# Logic_Level_Bidirectional.net
KiCad netlist of a schematic drawn in EAGLE
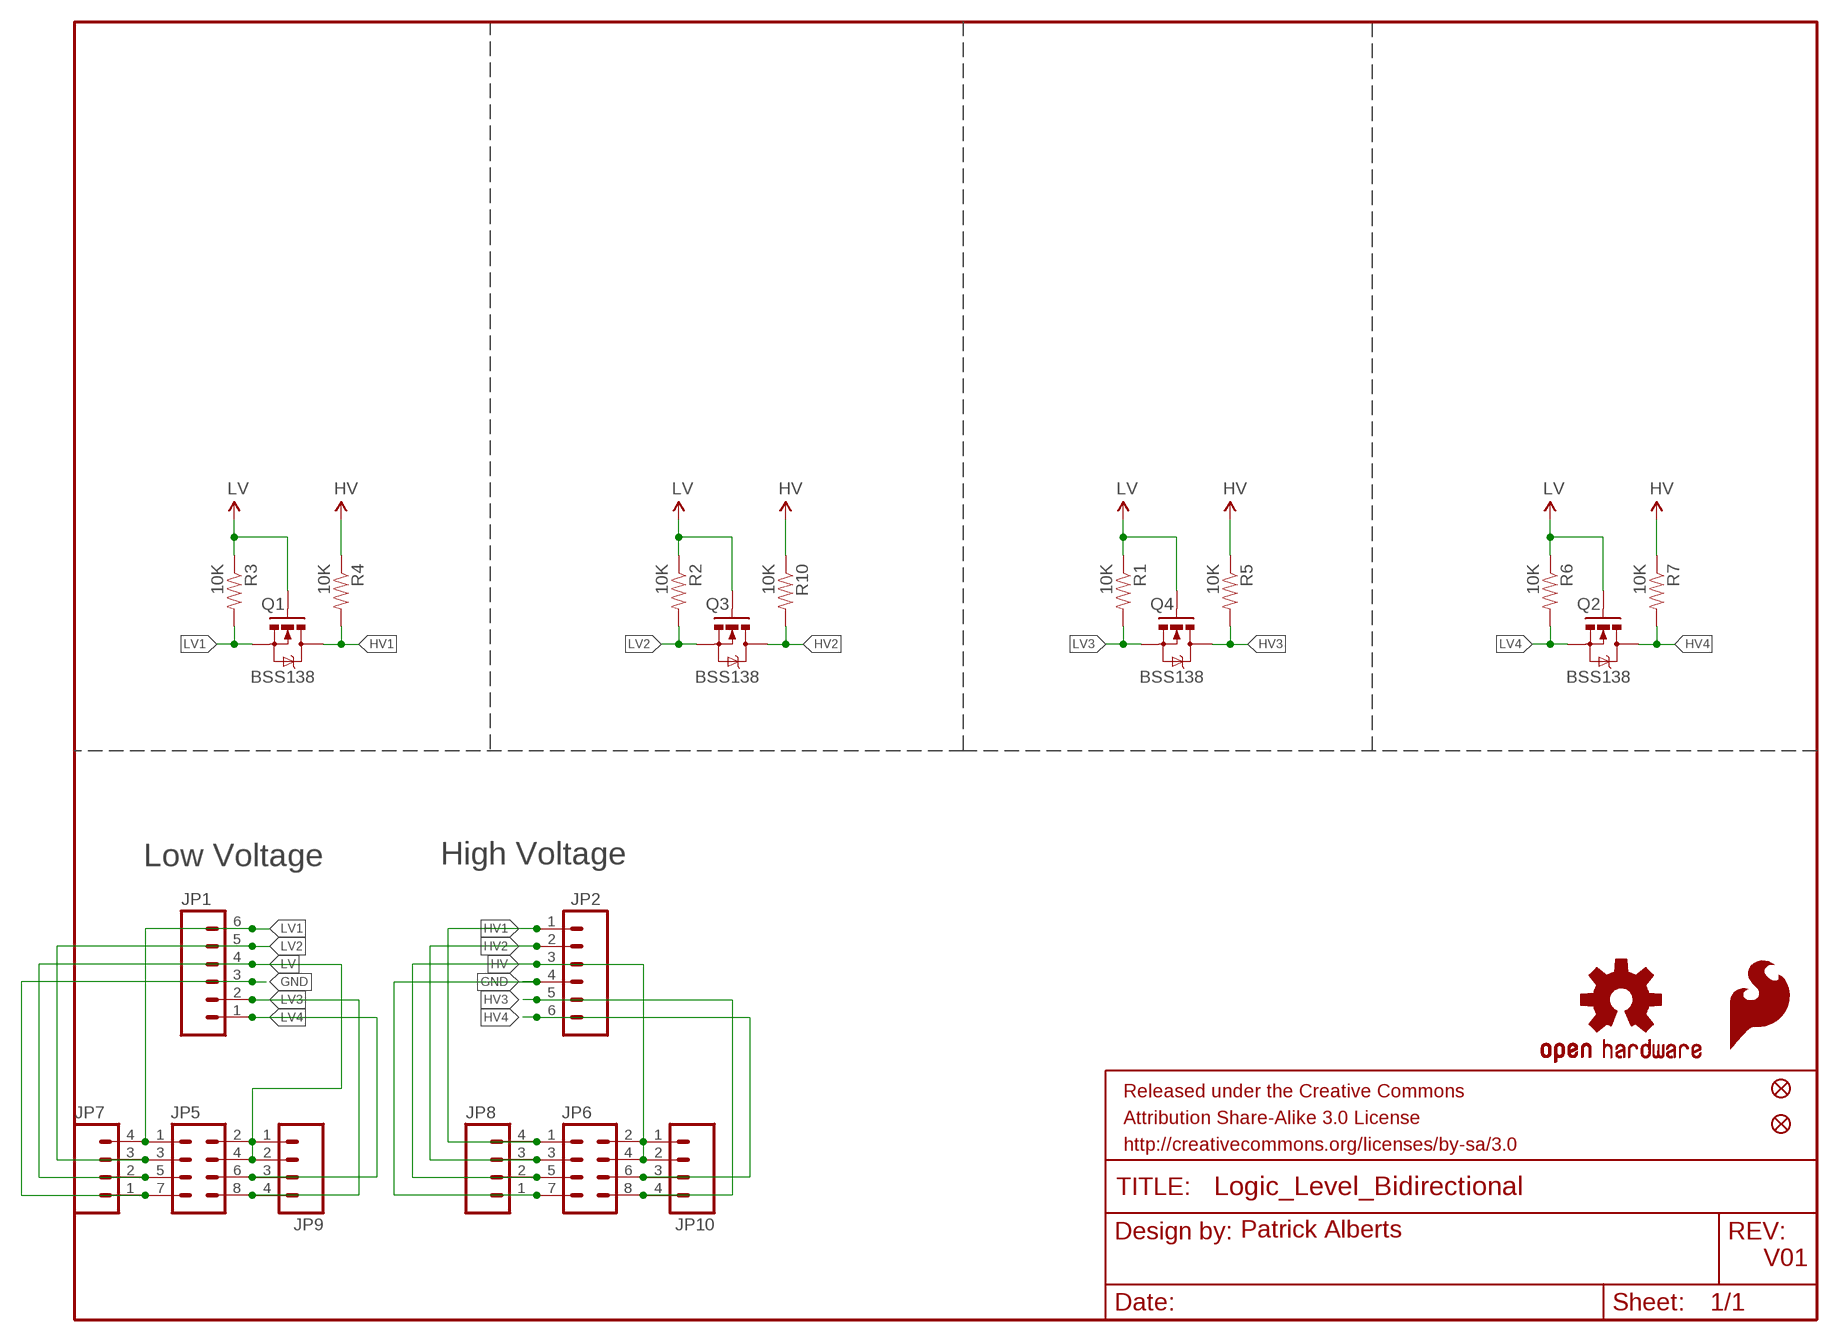
[diagram p0: schematic, sheet 1]

(export (version "E")
  (design (tool "Eeschema 10.0.6"))
  (components
    (comp (ref "JP1")
      (value "M06SIP")
      (footprint "eagle-import:1X06")
      (libsource (lib "eagle-import") (part "M06SIP"))
    )
    (comp (ref "JP2")
      (value "M06SIP")
      (footprint "eagle-import:1X06")
      (libsource (lib "eagle-import") (part "M06SIP"))
    )
    (comp (ref "JP3")
      (value "FIDUCIALUFIDUCIAL")
      (footprint "eagle-import:MICRO-FIDUCIAL")
      (libsource (lib "eagle-import") (part "FIDUCIALUFIDUCIAL"))
    )
    (comp (ref "JP4")
      (value "FIDUCIALUFIDUCIAL")
      (footprint "eagle-import:MICRO-FIDUCIAL")
      (libsource (lib "eagle-import") (part "FIDUCIALUFIDUCIAL"))
    )
    (comp (ref "JP5")
      (value "M04X2")
      (footprint "eagle-import:2X4")
      (libsource (lib "eagle-import") (part "M04X2"))
    )
    (comp (ref "JP6")
      (value "M04X2")
      (footprint "eagle-import:2X4")
      (libsource (lib "eagle-import") (part "M04X2"))
    )
    (comp (ref "JP7")
      (value "M04LOCK")
      (footprint "eagle-import:1X04_LOCK")
      (libsource (lib "eagle-import") (part "M04LOCK"))
    )
    (comp (ref "JP8")
      (value "M04LOCK")
      (footprint "eagle-import:1X04_LOCK")
      (libsource (lib "eagle-import") (part "M04LOCK"))
    )
    (comp (ref "JP9")
      (value "M04PTH")
      (footprint "eagle-import:1X04")
      (libsource (lib "eagle-import") (part "M04PTH"))
    )
    (comp (ref "JP10")
      (value "M04PTH")
      (footprint "eagle-import:1X04")
      (libsource (lib "eagle-import") (part "M04PTH"))
    )
    (comp (ref "LOGO1")
      (value "SFE_LOGO_FLAME.1_INCH")
      (footprint "eagle-import:SFE_LOGO_FLAME_.1")
      (libsource (lib "eagle-import") (part "SFE_LOGO_FLAME.1_INCH"))
    )
    (comp (ref "LOGO2")
      (value "OSHW-LOGOS")
      (footprint "eagle-import:OSHW-LOGO-S")
      (libsource (lib "eagle-import") (part "OSHW-LOGOS"))
    )
    (comp (ref "Q1")
      (value "BSS138")
      (footprint "eagle-import:SOT23-3")
      (libsource (lib "eagle-import") (part "MOSFET-NCHANNELSMD"))
    )
    (comp (ref "Q2")
      (value "BSS138")
      (footprint "eagle-import:SOT23-3")
      (libsource (lib "eagle-import") (part "MOSFET-NCHANNELSMD"))
    )
    (comp (ref "Q3")
      (value "BSS138")
      (footprint "eagle-import:SOT23-3")
      (libsource (lib "eagle-import") (part "MOSFET-NCHANNELSMD"))
    )
    (comp (ref "Q4")
      (value "BSS138")
      (footprint "eagle-import:SOT23-3")
      (libsource (lib "eagle-import") (part "MOSFET-NCHANNELSMD"))
    )
    (comp (ref "R1")
      (value "10K")
      (footprint "eagle-import:0603-RES")
      (libsource (lib "eagle-import") (part "RESISTOR0603-RES"))
    )
    (comp (ref "R2")
      (value "10K")
      (footprint "eagle-import:0603-RES")
      (libsource (lib "eagle-import") (part "RESISTOR0603-RES"))
    )
    (comp (ref "R3")
      (value "10K")
      (footprint "eagle-import:0603-RES")
      (libsource (lib "eagle-import") (part "RESISTOR0603-RES"))
    )
    (comp (ref "R4")
      (value "10K")
      (footprint "eagle-import:0603-RES")
      (libsource (lib "eagle-import") (part "RESISTOR0603-RES"))
    )
    (comp (ref "R5")
      (value "10K")
      (footprint "eagle-import:0603-RES")
      (libsource (lib "eagle-import") (part "RESISTOR0603-RES"))
    )
    (comp (ref "R6")
      (value "10K")
      (footprint "eagle-import:0603-RES")
      (libsource (lib "eagle-import") (part "RESISTOR0603-RES"))
    )
    (comp (ref "R7")
      (value "10K")
      (footprint "eagle-import:0603-RES")
      (libsource (lib "eagle-import") (part "RESISTOR0603-RES"))
    )
    (comp (ref "R10")
      (value "10K")
      (footprint "eagle-import:0603-RES")
      (libsource (lib "eagle-import") (part "RESISTOR0603-RES"))
    )
  )
  (nets
    (net (code "1") (name "GND") (class "Default")
      (node (ref "JP1") (pin "3") (pinfunction "3_3") (pintype "passive"))
      (node (ref "JP2") (pin "4") (pinfunction "4_4") (pintype "passive"))
      (node (ref "JP5") (pin "7") (pinfunction "7_7") (pintype "passive"))
      (node (ref "JP6") (pin "7") (pinfunction "7_7") (pintype "passive"))
      (node (ref "JP7") (pin "1") (pinfunction "1_1") (pintype "passive"))
      (node (ref "JP8") (pin "1") (pinfunction "1_1") (pintype "passive"))
    )
    (net (code "2") (name "HV") (class "Default")
      (node (ref "JP10") (pin "1") (pinfunction "1_1") (pintype "passive"))
      (node (ref "JP10") (pin "2") (pinfunction "2_2") (pintype "passive"))
      (node (ref "JP2") (pin "3") (pinfunction "3_3") (pintype "passive"))
      (node (ref "JP6") (pin "2") (pinfunction "2_2") (pintype "passive"))
      (node (ref "JP6") (pin "4") (pinfunction "4_4") (pintype "passive"))
      (node (ref "JP6") (pin "5") (pinfunction "5_5") (pintype "passive"))
      (node (ref "JP8") (pin "2") (pinfunction "2_2") (pintype "passive"))
      (node (ref "R10") (pin "1") (pinfunction "1_1") (pintype "passive"))
      (node (ref "R4") (pin "1") (pinfunction "1_1") (pintype "passive"))
      (node (ref "R5") (pin "1") (pinfunction "1_1") (pintype "passive"))
      (node (ref "R7") (pin "1") (pinfunction "1_1") (pintype "passive"))
    )
    (net (code "3") (name "HV1") (class "Default")
      (node (ref "JP2") (pin "1") (pinfunction "1_1") (pintype "passive"))
      (node (ref "JP6") (pin "1") (pinfunction "1_1") (pintype "passive"))
      (node (ref "JP8") (pin "4") (pinfunction "4_4") (pintype "passive"))
      (node (ref "Q1") (pin "3") (pinfunction "D_3") (pintype "passive"))
      (node (ref "R4") (pin "2") (pinfunction "2_2") (pintype "passive"))
    )
    (net (code "4") (name "HV2") (class "Default")
      (node (ref "JP2") (pin "2") (pinfunction "2_2") (pintype "passive"))
      (node (ref "JP6") (pin "3") (pinfunction "3_3") (pintype "passive"))
      (node (ref "JP8") (pin "3") (pinfunction "3_3") (pintype "passive"))
      (node (ref "Q3") (pin "3") (pinfunction "D_3") (pintype "passive"))
      (node (ref "R10") (pin "2") (pinfunction "2_2") (pintype "passive"))
    )
    (net (code "5") (name "HV3") (class "Default")
      (node (ref "JP10") (pin "4") (pinfunction "4_4") (pintype "passive"))
      (node (ref "JP2") (pin "5") (pinfunction "5_5") (pintype "passive"))
      (node (ref "JP6") (pin "8") (pinfunction "8_8") (pintype "passive"))
      (node (ref "Q4") (pin "3") (pinfunction "D_3") (pintype "passive"))
      (node (ref "R5") (pin "2") (pinfunction "2_2") (pintype "passive"))
    )
    (net (code "6") (name "HV4") (class "Default")
      (node (ref "JP10") (pin "3") (pinfunction "3_3") (pintype "passive"))
      (node (ref "JP2") (pin "6") (pinfunction "6_6") (pintype "passive"))
      (node (ref "JP6") (pin "6") (pinfunction "6_6") (pintype "passive"))
      (node (ref "Q2") (pin "3") (pinfunction "D_3") (pintype "passive"))
      (node (ref "R7") (pin "2") (pinfunction "2_2") (pintype "passive"))
    )
    (net (code "7") (name "LV") (class "Default")
      (node (ref "JP1") (pin "4") (pinfunction "4_4") (pintype "passive"))
      (node (ref "JP5") (pin "2") (pinfunction "2_2") (pintype "passive"))
      (node (ref "JP5") (pin "4") (pinfunction "4_4") (pintype "passive"))
      (node (ref "JP5") (pin "5") (pinfunction "5_5") (pintype "passive"))
      (node (ref "JP7") (pin "2") (pinfunction "2_2") (pintype "passive"))
      (node (ref "JP9") (pin "1") (pinfunction "1_1") (pintype "passive"))
      (node (ref "JP9") (pin "2") (pinfunction "2_2") (pintype "passive"))
      (node (ref "Q1") (pin "1") (pinfunction "G_1") (pintype "passive"))
      (node (ref "Q2") (pin "1") (pinfunction "G_1") (pintype "passive"))
      (node (ref "Q3") (pin "1") (pinfunction "G_1") (pintype "passive"))
      (node (ref "Q4") (pin "1") (pinfunction "G_1") (pintype "passive"))
      (node (ref "R1") (pin "1") (pinfunction "1_1") (pintype "passive"))
      (node (ref "R2") (pin "1") (pinfunction "1_1") (pintype "passive"))
      (node (ref "R3") (pin "1") (pinfunction "1_1") (pintype "passive"))
      (node (ref "R6") (pin "1") (pinfunction "1_1") (pintype "passive"))
    )
    (net (code "8") (name "LV1") (class "Default")
      (node (ref "JP1") (pin "6") (pinfunction "6_6") (pintype "passive"))
      (node (ref "JP5") (pin "1") (pinfunction "1_1") (pintype "passive"))
      (node (ref "JP7") (pin "4") (pinfunction "4_4") (pintype "passive"))
      (node (ref "Q1") (pin "2") (pinfunction "S_2") (pintype "passive"))
      (node (ref "R3") (pin "2") (pinfunction "2_2") (pintype "passive"))
    )
    (net (code "9") (name "LV2") (class "Default")
      (node (ref "JP1") (pin "5") (pinfunction "5_5") (pintype "passive"))
      (node (ref "JP5") (pin "3") (pinfunction "3_3") (pintype "passive"))
      (node (ref "JP7") (pin "3") (pinfunction "3_3") (pintype "passive"))
      (node (ref "Q3") (pin "2") (pinfunction "S_2") (pintype "passive"))
      (node (ref "R2") (pin "2") (pinfunction "2_2") (pintype "passive"))
    )
    (net (code "10") (name "LV3") (class "Default")
      (node (ref "JP1") (pin "2") (pinfunction "2_2") (pintype "passive"))
      (node (ref "JP5") (pin "8") (pinfunction "8_8") (pintype "passive"))
      (node (ref "JP9") (pin "4") (pinfunction "4_4") (pintype "passive"))
      (node (ref "Q4") (pin "2") (pinfunction "S_2") (pintype "passive"))
      (node (ref "R1") (pin "2") (pinfunction "2_2") (pintype "passive"))
    )
    (net (code "11") (name "LV4") (class "Default")
      (node (ref "JP1") (pin "1") (pinfunction "1_1") (pintype "passive"))
      (node (ref "JP5") (pin "6") (pinfunction "6_6") (pintype "passive"))
      (node (ref "JP9") (pin "3") (pinfunction "3_3") (pintype "passive"))
      (node (ref "Q2") (pin "2") (pinfunction "S_2") (pintype "passive"))
      (node (ref "R6") (pin "2") (pinfunction "2_2") (pintype "passive"))
    )
  )
)
